# final-board.net
KiCad netlist of a schematic drawn in EAGLE
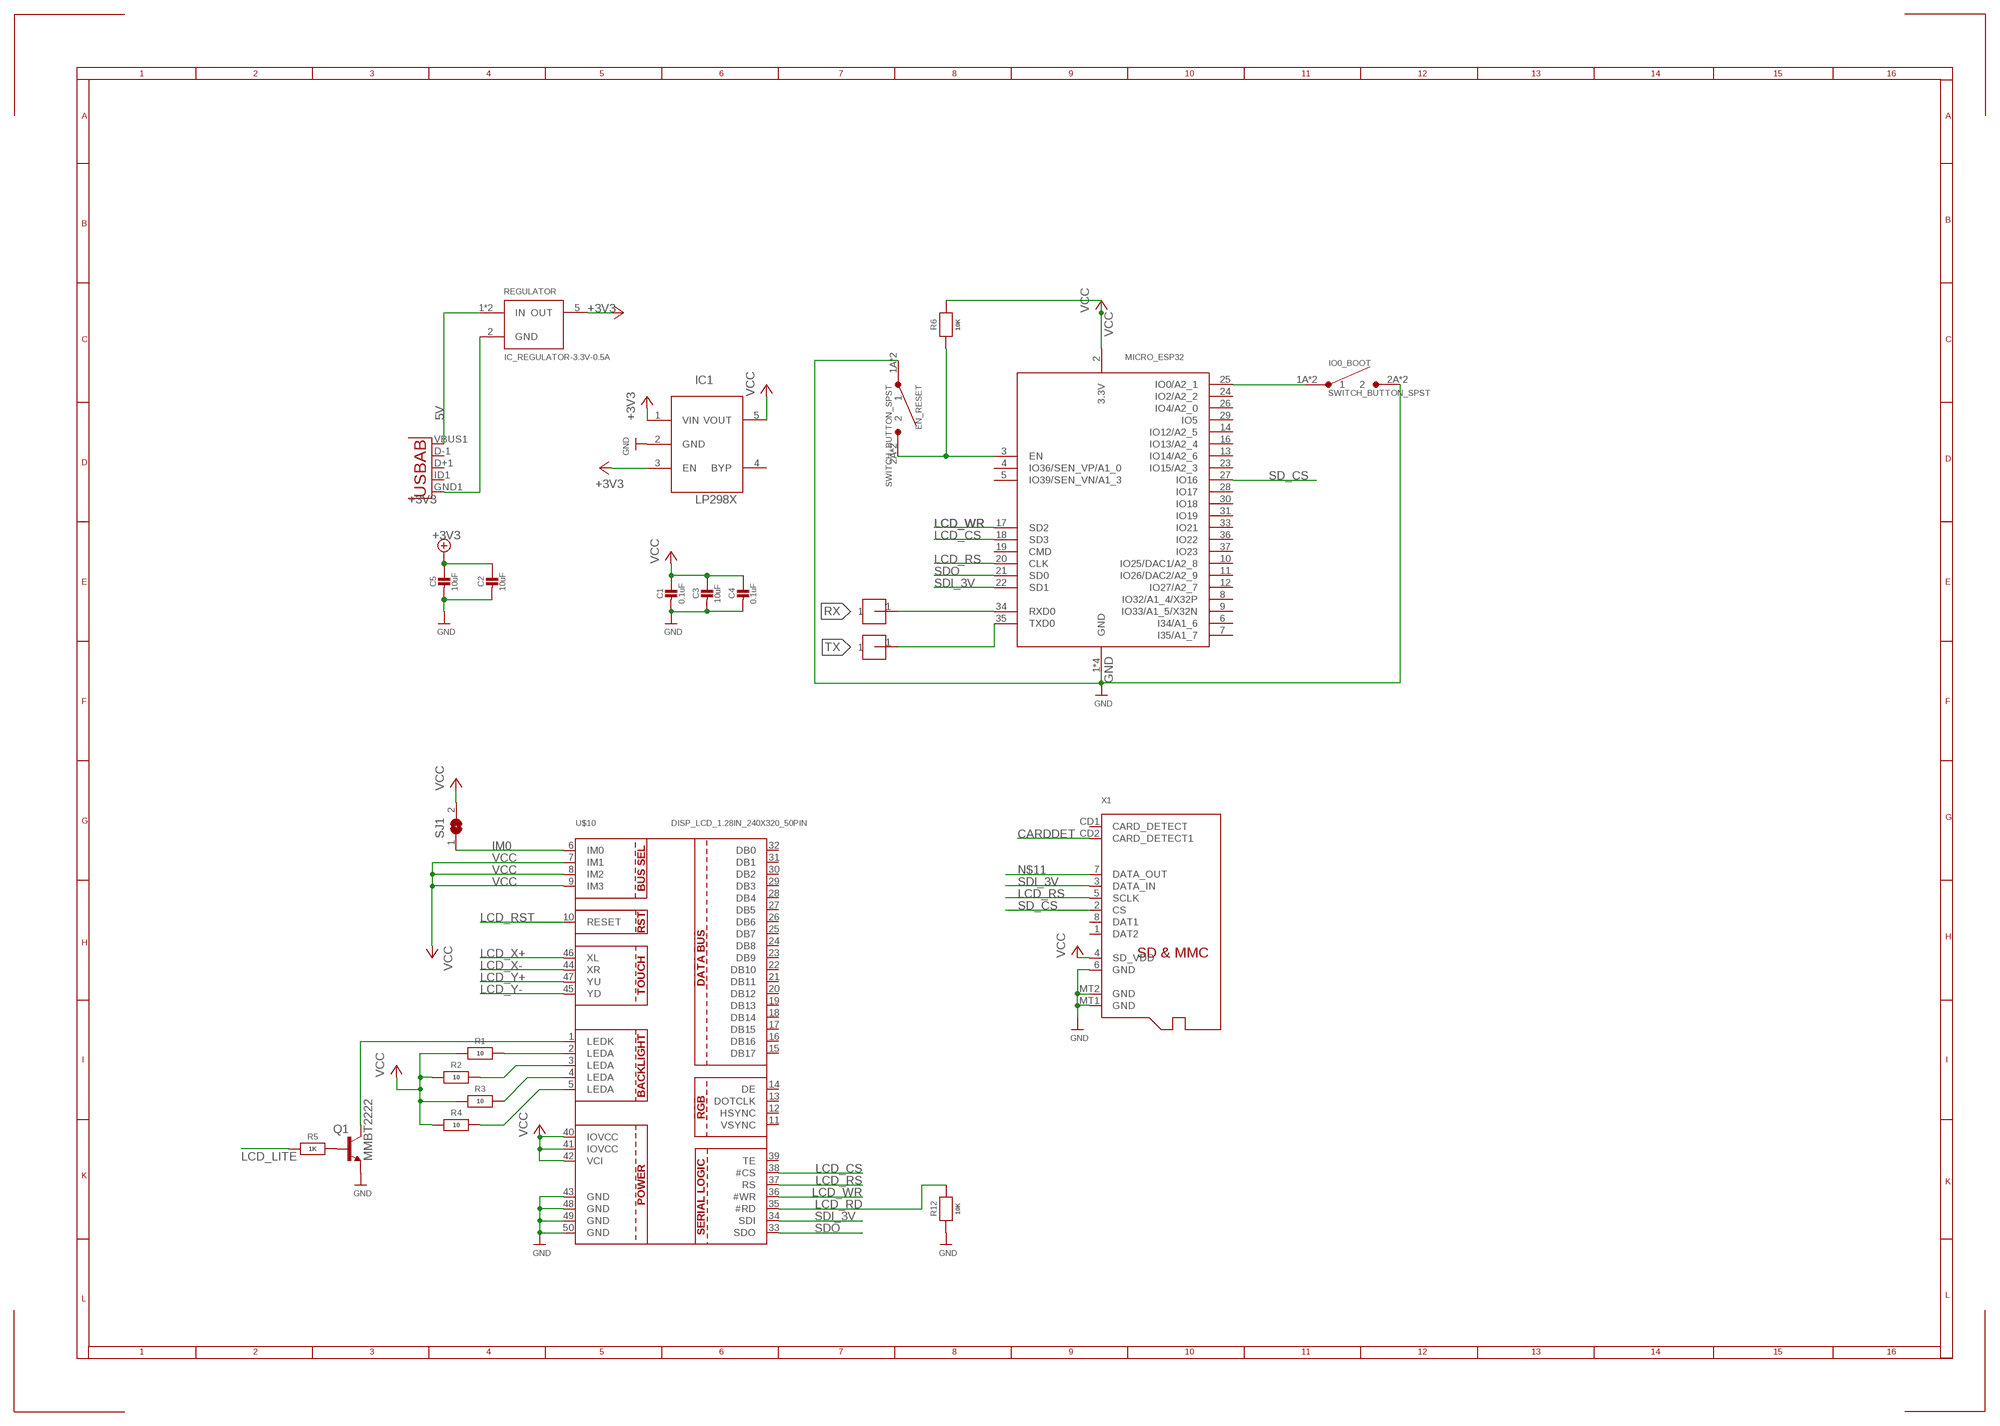
[diagram p0: schematic, sheet 1]

(export (version "E")
  (design (tool "Eeschema 10.0.6"))
  (components
    (comp (ref "C1")
      (value "0.1uF")
      (footprint "eagle-import:0805-NO")
      (libsource (lib "eagle-import") (part "CAP_CERAMIC0805-NOOUTLINE"))
    )
    (comp (ref "C2")
      (value "10uF")
      (footprint "eagle-import:0805-NO")
      (libsource (lib "eagle-import") (part "CAP_CERAMIC0805-NOOUTLINE"))
    )
    (comp (ref "C3")
      (value "10uF")
      (footprint "eagle-import:0805-NO")
      (libsource (lib "eagle-import") (part "CAP_CERAMIC0805-NOOUTLINE"))
    )
    (comp (ref "C4")
      (value "0.1uF")
      (footprint "eagle-import:0805-NO")
      (libsource (lib "eagle-import") (part "CAP_CERAMIC0805-NOOUTLINE"))
    )
    (comp (ref "C5")
      (value "10uF")
      (footprint "eagle-import:0805-NO")
      (libsource (lib "eagle-import") (part "CAP_CERAMIC0805-NOOUTLINE"))
    )
    (comp (ref "EN_RESET")
      (value "SWITCH_BUTTON_SPST")
      (footprint "eagle-import:7914G-1-000E")
      (libsource (lib "eagle-import") (part "SWITCH_BUTTON_SPST"))
    )
    (comp (ref "ESP_32")
      (value "MICRO_ESP32")
      (footprint "eagle-import:WROOM32")
      (libsource (lib "eagle-import") (part "MICRO_ESP32"))
    )
    (comp (ref "IC1")
      (value "MIC5225-3.3")
      (footprint "eagle-import:SOT23-5L")
      (libsource (lib "eagle-import") (part "LP298XS"))
    )
    (comp (ref "IO0_BOOT")
      (value "SWITCH_BUTTON_SPST")
      (footprint "eagle-import:7914G-1-000E")
      (libsource (lib "eagle-import") (part "SWITCH_BUTTON_SPST"))
    )
    (comp (ref "Q1")
      (value "MMBT2222")
      (footprint "eagle-import:SOT23-BEC")
      (libsource (lib "eagle-import") (part "-NPN-SOT23-BECMMBT2222ALT1"))
    )
    (comp (ref "R1")
      (value "10")
      (footprint "eagle-import:0805-NO")
      (libsource (lib "eagle-import") (part "RESISTOR0805_NOOUTLINE"))
    )
    (comp (ref "R2")
      (value "10")
      (footprint "eagle-import:0805-NO")
      (libsource (lib "eagle-import") (part "RESISTOR0805_NOOUTLINE"))
    )
    (comp (ref "R3")
      (value "10")
      (footprint "eagle-import:0805-NO")
      (libsource (lib "eagle-import") (part "RESISTOR0805_NOOUTLINE"))
    )
    (comp (ref "R4")
      (value "10")
      (footprint "eagle-import:0805-NO")
      (libsource (lib "eagle-import") (part "RESISTOR0805_NOOUTLINE"))
    )
    (comp (ref "R5")
      (value "1K")
      (footprint "eagle-import:0805-NO")
      (libsource (lib "eagle-import") (part "RESISTOR0805_NOOUTLINE"))
    )
    (comp (ref "R6")
      (value "10K")
      (footprint "eagle-import:0805-NO")
      (libsource (lib "eagle-import") (part "RESISTOR0805_NOOUTLINE"))
    )
    (comp (ref "R12")
      (value "10K")
      (footprint "eagle-import:0805-NO")
      (libsource (lib "eagle-import") (part "RESISTOR0805_NOOUTLINE"))
    )
    (comp (ref "REGULATOR")
      (value "IC_REGULATOR-3.3V-0.5A")
      (footprint "eagle-import:SOT23-5")
      (libsource (lib "eagle-import") (part "IC_REGULATOR-3.3V-0.5A"))
    )
    (comp (ref "SJ1")
      (value "SOLDERJUMPER")
      (footprint "eagle-import:SOLDERJUMPER_ARROW_NOPASTE")
      (libsource (lib "eagle-import") (part "SOLDERJUMPER"))
    )
    (comp (ref "U$2")
      (value "HEADER-1-TESTPOINT")
      (footprint "eagle-import:TESTPOINT-1")
      (libsource (lib "eagle-import") (part "HEADER-1-TESTPOINT"))
    )
    (comp (ref "U$7")
      (value "HEADER-1-TESTPOINT")
      (footprint "eagle-import:TESTPOINT-1")
      (libsource (lib "eagle-import") (part "HEADER-1-TESTPOINT"))
    )
    (comp (ref "U$10")
      (value "DISP_LCD_1.28IN_240X320_50PIN")
      (footprint "eagle-import:TFT_2.83IN_240X320_50PIN")
      (libsource (lib "eagle-import") (part "DISP_LCD_1.28IN_240X320_50PIN"))
    )
    (comp (ref "USB")
      (value "USB\"\"")
      (footprint "eagle-import:USB-MICRO-SMD")
      (libsource (lib "eagle-import") (part "USB{dblquote}{dblquote}"))
    )
    (comp (ref "X1")
      (value "MICROSD")
      (footprint "eagle-import:MICROSD")
      (libsource (lib "eagle-import") (part "MICROSD"))
    )
  )
  (nets
    (net (code "1") (name "+3V3") (class "Default")
      (node (ref "C2") (pin "1") (pinfunction "1_1") (pintype "passive"))
      (node (ref "C5") (pin "1") (pinfunction "1_1") (pintype "passive"))
      (node (ref "IC1") (pin "1") (pinfunction "VIN_1") (pintype "bidirectional"))
      (node (ref "IC1") (pin "3") (pinfunction "EN_3") (pintype "bidirectional"))
      (node (ref "REGULATOR") (pin "5") (pinfunction "OUT_5") (pintype "bidirectional"))
    )
    (net (code "2") (name "/5V") (class "Default")
      (node (ref "REGULATOR") (pin "1") (pinfunction "IN_1") (pintype "bidirectional"))
      (node (ref "REGULATOR") (pin "3") (pinfunction "IN_3") (pintype "bidirectional"))
      (node (ref "USB") (pin "VBUS1") (pinfunction "VBUS_VBUS1") (pintype "bidirectional"))
    )
    (net (code "3") (name "/CARDDET") (class "Default")
      (node (ref "X1") (pin "CD2") (pinfunction "CARD_DETECT1_CD2") (pintype "passive"))
    )
    (net (code "4") (name "/IM0") (class "Default")
      (node (ref "SJ1") (pin "1") (pinfunction "1_1") (pintype "passive"))
      (node (ref "U$10") (pin "6") (pinfunction "IM0_6") (pintype "bidirectional"))
    )
    (net (code "5") (name "/LCD_CS") (class "Default")
      (node (ref "ESP_32") (pin "18") (pinfunction "SD3_18") (pintype "bidirectional"))
      (node (ref "U$10") (pin "38") (pinfunction "#CS_38") (pintype "bidirectional"))
    )
    (net (code "6") (name "/LCD_LITE") (class "Default")
      (node (ref "R5") (pin "1") (pinfunction "1_1") (pintype "passive"))
    )
    (net (code "7") (name "/LCD_RD") (class "Default")
      (node (ref "R12") (pin "2") (pinfunction "2_2") (pintype "passive"))
      (node (ref "U$10") (pin "35") (pinfunction "#RD_35") (pintype "bidirectional"))
    )
    (net (code "8") (name "/LCD_RS") (class "Default")
      (node (ref "ESP_32") (pin "20") (pinfunction "CLK_20") (pintype "bidirectional"))
      (node (ref "U$10") (pin "37") (pinfunction "RS_37") (pintype "bidirectional"))
      (node (ref "X1") (pin "5") (pinfunction "SCLK_5") (pintype "input"))
    )
    (net (code "9") (name "/LCD_RST") (class "Default")
      (node (ref "U$10") (pin "10") (pinfunction "RESET_10") (pintype "bidirectional"))
    )
    (net (code "10") (name "/LCD_WR") (class "Default")
      (node (ref "ESP_32") (pin "17") (pinfunction "SD2_17") (pintype "bidirectional"))
      (node (ref "U$10") (pin "36") (pinfunction "#WR_36") (pintype "bidirectional"))
    )
    (net (code "11") (name "/LCD_X+") (class "Default")
      (node (ref "U$10") (pin "46") (pinfunction "XL_46") (pintype "bidirectional"))
    )
    (net (code "12") (name "/LCD_X-") (class "Default")
      (node (ref "U$10") (pin "44") (pinfunction "XR_44") (pintype "bidirectional"))
    )
    (net (code "13") (name "/LCD_Y+") (class "Default")
      (node (ref "U$10") (pin "47") (pinfunction "YU_47") (pintype "bidirectional"))
    )
    (net (code "14") (name "/LCD_Y-") (class "Default")
      (node (ref "U$10") (pin "45") (pinfunction "YD_45") (pintype "bidirectional"))
    )
    (net (code "15") (name "/N$11") (class "Default")
      (node (ref "X1") (pin "7") (pinfunction "DATA_OUT_7") (pintype "output"))
    )
    (net (code "16") (name "/SDI_3V") (class "Default")
      (node (ref "ESP_32") (pin "22") (pinfunction "SD1_22") (pintype "bidirectional"))
      (node (ref "U$10") (pin "34") (pinfunction "SDI_34") (pintype "bidirectional"))
      (node (ref "X1") (pin "3") (pinfunction "DATA_IN_3") (pintype "input"))
    )
    (net (code "17") (name "/SDO") (class "Default")
      (node (ref "ESP_32") (pin "21") (pinfunction "SD0_21") (pintype "bidirectional"))
      (node (ref "U$10") (pin "33") (pinfunction "SDO_33") (pintype "bidirectional"))
    )
    (net (code "18") (name "/SD_CS") (class "Default")
      (node (ref "ESP_32") (pin "27") (pinfunction "IO16_27") (pintype "bidirectional"))
      (node (ref "X1") (pin "2") (pinfunction "CS_2") (pintype "input"))
    )
    (net (code "19") (name "GND") (class "Default")
      (node (ref "C1") (pin "2") (pinfunction "2_2") (pintype "passive"))
      (node (ref "C2") (pin "2") (pinfunction "2_2") (pintype "passive"))
      (node (ref "C3") (pin "2") (pinfunction "2_2") (pintype "passive"))
      (node (ref "C4") (pin "2") (pinfunction "2_2") (pintype "passive"))
      (node (ref "C5") (pin "2") (pinfunction "2_2") (pintype "passive"))
      (node (ref "EN_RESET") (pin "1A") (pinfunction "1_1A") (pintype "bidirectional"))
      (node (ref "EN_RESET") (pin "1B") (pinfunction "1_1B") (pintype "bidirectional"))
      (node (ref "ESP_32") (pin "1") (pinfunction "GND_1") (pintype "passive"))
      (node (ref "ESP_32") (pin "15") (pinfunction "GND_15") (pintype "passive"))
      (node (ref "ESP_32") (pin "38") (pinfunction "GND_38") (pintype "passive"))
      (node (ref "ESP_32") (pin "P$1") (pinfunction "GND_P$1") (pintype "passive"))
      (node (ref "IC1") (pin "2") (pinfunction "GND_2") (pintype "bidirectional"))
      (node (ref "IO0_BOOT") (pin "2A") (pinfunction "2_2A") (pintype "bidirectional"))
      (node (ref "IO0_BOOT") (pin "2B") (pinfunction "2_2B") (pintype "bidirectional"))
      (node (ref "Q1") (pin "E") (pinfunction "E_E") (pintype "passive"))
      (node (ref "R12") (pin "1") (pinfunction "1_1") (pintype "passive"))
      (node (ref "REGULATOR") (pin "2") (pinfunction "GND_2") (pintype "bidirectional"))
      (node (ref "U$10") (pin "43") (pinfunction "GND_43") (pintype "bidirectional"))
      (node (ref "U$10") (pin "48") (pinfunction "GND_48") (pintype "bidirectional"))
      (node (ref "U$10") (pin "49") (pinfunction "GND_49") (pintype "bidirectional"))
      (node (ref "U$10") (pin "50") (pinfunction "GND_50") (pintype "bidirectional"))
      (node (ref "USB") (pin "GND1") (pinfunction "GND_GND1") (pintype "bidirectional"))
      (node (ref "X1") (pin "6") (pinfunction "GND_6") (pintype "power_in"))
      (node (ref "X1") (pin "MT1") (pinfunction "GND_MT1") (pintype "power_in"))
      (node (ref "X1") (pin "MT2") (pinfunction "GND_MT2") (pintype "power_in"))
    )
    (net (code "20") (name "Net-(ESP_32-EN)") (class "Default")
      (node (ref "EN_RESET") (pin "2A") (pinfunction "2_2A") (pintype "bidirectional"))
      (node (ref "EN_RESET") (pin "2B") (pinfunction "2_2B") (pintype "bidirectional"))
      (node (ref "ESP_32") (pin "3") (pinfunction "EN_3") (pintype "input"))
      (node (ref "R6") (pin "1") (pinfunction "1_1") (pintype "passive"))
    )
    (net (code "21") (name "Net-(ESP_32-IO0{slash}A2_1)") (class "Default")
      (node (ref "ESP_32") (pin "25") (pinfunction "IO0/A2_1_25") (pintype "bidirectional"))
      (node (ref "IO0_BOOT") (pin "1A") (pinfunction "1_1A") (pintype "bidirectional"))
      (node (ref "IO0_BOOT") (pin "1B") (pinfunction "1_1B") (pintype "bidirectional"))
    )
    (net (code "22") (name "Net-(Q1-PadB)") (class "Default")
      (node (ref "Q1") (pin "B") (pinfunction "B_B") (pintype "passive"))
      (node (ref "R5") (pin "2") (pinfunction "2_2") (pintype "passive"))
    )
    (net (code "23") (name "Net-(R1-Pad2)") (class "Default")
      (node (ref "R1") (pin "2") (pinfunction "2_2") (pintype "passive"))
      (node (ref "U$10") (pin "2") (pinfunction "LEDA_2") (pintype "bidirectional"))
    )
    (net (code "24") (name "Net-(R2-Pad2)") (class "Default")
      (node (ref "R2") (pin "2") (pinfunction "2_2") (pintype "passive"))
      (node (ref "U$10") (pin "3") (pinfunction "LEDA_3") (pintype "bidirectional"))
    )
    (net (code "25") (name "Net-(R3-Pad2)") (class "Default")
      (node (ref "R3") (pin "2") (pinfunction "2_2") (pintype "passive"))
      (node (ref "U$10") (pin "4") (pinfunction "LEDA_4") (pintype "bidirectional"))
    )
    (net (code "26") (name "Net-(R4-Pad2)") (class "Default")
      (node (ref "R4") (pin "2") (pinfunction "2_2") (pintype "passive"))
      (node (ref "U$10") (pin "5") (pinfunction "LEDA_5") (pintype "bidirectional"))
    )
    (net (code "27") (name "Net-(U$10-LEDK)") (class "Default")
      (node (ref "Q1") (pin "C") (pinfunction "C_C") (pintype "passive"))
      (node (ref "U$10") (pin "1") (pinfunction "LEDK_1") (pintype "bidirectional"))
    )
    (net (code "28") (name "RX") (class "Default")
      (node (ref "ESP_32") (pin "34") (pinfunction "RXD0_34") (pintype "input"))
      (node (ref "U$2") (pin "1") (pinfunction "1_1") (pintype "bidirectional"))
    )
    (net (code "29") (name "TX") (class "Default")
      (node (ref "ESP_32") (pin "35") (pinfunction "TXD0_35") (pintype "output"))
      (node (ref "U$7") (pin "1") (pinfunction "1_1") (pintype "bidirectional"))
    )
    (net (code "30") (name "VCC") (class "Default")
      (node (ref "C1") (pin "1") (pinfunction "1_1") (pintype "passive"))
      (node (ref "C3") (pin "1") (pinfunction "1_1") (pintype "passive"))
      (node (ref "C4") (pin "1") (pinfunction "1_1") (pintype "passive"))
      (node (ref "ESP_32") (pin "2") (pinfunction "3.3V_2") (pintype "passive"))
      (node (ref "IC1") (pin "5") (pinfunction "VOUT_5") (pintype "bidirectional"))
      (node (ref "R1") (pin "1") (pinfunction "1_1") (pintype "passive"))
      (node (ref "R2") (pin "1") (pinfunction "1_1") (pintype "passive"))
      (node (ref "R3") (pin "1") (pinfunction "1_1") (pintype "passive"))
      (node (ref "R4") (pin "1") (pinfunction "1_1") (pintype "passive"))
      (node (ref "R6") (pin "2") (pinfunction "2_2") (pintype "passive"))
      (node (ref "SJ1") (pin "2") (pinfunction "2_2") (pintype "passive"))
      (node (ref "U$10") (pin "40") (pinfunction "IOVCC_40") (pintype "bidirectional"))
      (node (ref "U$10") (pin "41") (pinfunction "IOVCC_41") (pintype "bidirectional"))
      (node (ref "U$10") (pin "42") (pinfunction "VCI_42") (pintype "bidirectional"))
      (node (ref "U$10") (pin "7") (pinfunction "IM1_7") (pintype "bidirectional"))
      (node (ref "U$10") (pin "8") (pinfunction "IM2_8") (pintype "bidirectional"))
      (node (ref "U$10") (pin "9") (pinfunction "IM3_9") (pintype "bidirectional"))
      (node (ref "X1") (pin "4") (pinfunction "SD_VDD_4") (pintype "power_in"))
    )
    (net (code "31") (name "unconnected-(ESP_32-CMD-Pad19)") (class "Default")
      (node (ref "ESP_32") (pin "19") (pinfunction "CMD_19") (pintype "bidirectional"))
    )
    (net (code "32") (name "unconnected-(ESP_32-I34{slash}A1_6-Pad6)") (class "Default")
      (node (ref "ESP_32") (pin "6") (pinfunction "I34/A1_6_6") (pintype "bidirectional"))
    )
    (net (code "33") (name "unconnected-(ESP_32-I35{slash}A1_7-Pad7)") (class "Default")
      (node (ref "ESP_32") (pin "7") (pinfunction "I35/A1_7_7") (pintype "bidirectional"))
    )
    (net (code "34") (name "unconnected-(ESP_32-IO2{slash}A2_2-Pad24)") (class "Default")
      (node (ref "ESP_32") (pin "24") (pinfunction "IO2/A2_2_24") (pintype "bidirectional"))
    )
    (net (code "35") (name "unconnected-(ESP_32-IO4{slash}A2_0-Pad26)") (class "Default")
      (node (ref "ESP_32") (pin "26") (pinfunction "IO4/A2_0_26") (pintype "bidirectional"))
    )
    (net (code "36") (name "unconnected-(ESP_32-IO5-Pad29)") (class "Default")
      (node (ref "ESP_32") (pin "29") (pinfunction "IO5_29") (pintype "bidirectional"))
    )
    (net (code "37") (name "unconnected-(ESP_32-IO12{slash}A2_5-Pad14)") (class "Default")
      (node (ref "ESP_32") (pin "14") (pinfunction "IO12/A2_5_14") (pintype "bidirectional"))
    )
    (net (code "38") (name "unconnected-(ESP_32-IO13{slash}A2_4-Pad16)") (class "Default")
      (node (ref "ESP_32") (pin "16") (pinfunction "IO13/A2_4_16") (pintype "bidirectional"))
    )
    (net (code "39") (name "unconnected-(ESP_32-IO14{slash}A2_6-Pad13)") (class "Default")
      (node (ref "ESP_32") (pin "13") (pinfunction "IO14/A2_6_13") (pintype "bidirectional"))
    )
    (net (code "40") (name "unconnected-(ESP_32-IO15{slash}A2_3-Pad23)") (class "Default")
      (node (ref "ESP_32") (pin "23") (pinfunction "IO15/A2_3_23") (pintype "bidirectional"))
    )
    (net (code "41") (name "unconnected-(ESP_32-IO17-Pad28)") (class "Default")
      (node (ref "ESP_32") (pin "28") (pinfunction "IO17_28") (pintype "bidirectional"))
    )
    (net (code "42") (name "unconnected-(ESP_32-IO18-Pad30)") (class "Default")
      (node (ref "ESP_32") (pin "30") (pinfunction "IO18_30") (pintype "bidirectional"))
    )
    (net (code "43") (name "unconnected-(ESP_32-IO19-Pad31)") (class "Default")
      (node (ref "ESP_32") (pin "31") (pinfunction "IO19_31") (pintype "bidirectional"))
    )
    (net (code "44") (name "unconnected-(ESP_32-IO21-Pad33)") (class "Default")
      (node (ref "ESP_32") (pin "33") (pinfunction "IO21_33") (pintype "bidirectional"))
    )
    (net (code "45") (name "unconnected-(ESP_32-IO22-Pad36)") (class "Default")
      (node (ref "ESP_32") (pin "36") (pinfunction "IO22_36") (pintype "bidirectional"))
    )
    (net (code "46") (name "unconnected-(ESP_32-IO23-Pad37)") (class "Default")
      (node (ref "ESP_32") (pin "37") (pinfunction "IO23_37") (pintype "bidirectional"))
    )
    (net (code "47") (name "unconnected-(ESP_32-IO25{slash}DAC1{slash}A2_8-Pad10)") (class "Default")
      (node (ref "ESP_32") (pin "10") (pinfunction "IO25/DAC1/A2_8_10") (pintype "bidirectional"))
    )
    (net (code "48") (name "unconnected-(ESP_32-IO26{slash}DAC2{slash}A2_9-Pad11)") (class "Default")
      (node (ref "ESP_32") (pin "11") (pinfunction "IO26/DAC2/A2_9_11") (pintype "bidirectional"))
    )
    (net (code "49") (name "unconnected-(ESP_32-IO27{slash}A2_7-Pad12)") (class "Default")
      (node (ref "ESP_32") (pin "12") (pinfunction "IO27/A2_7_12") (pintype "bidirectional"))
    )
    (net (code "50") (name "unconnected-(ESP_32-IO32{slash}A1_4{slash}X32P-Pad8)") (class "Default")
      (node (ref "ESP_32") (pin "8") (pinfunction "IO32/A1_4/X32P_8") (pintype "bidirectional"))
    )
    (net (code "51") (name "unconnected-(ESP_32-IO33{slash}A1_5{slash}X32N-Pad9)") (class "Default")
      (node (ref "ESP_32") (pin "9") (pinfunction "IO33/A1_5/X32N_9") (pintype "bidirectional"))
    )
    (net (code "52") (name "unconnected-(ESP_32-IO36{slash}SEN_VP{slash}A1_0-Pad4)") (class "Default")
      (node (ref "ESP_32") (pin "4") (pinfunction "IO36/SEN_VP/A1_0_4") (pintype "passive"))
    )
    (net (code "53") (name "unconnected-(ESP_32-IO39{slash}SEN_VN{slash}A1_3-Pad5)") (class "Default")
      (node (ref "ESP_32") (pin "5") (pinfunction "IO39/SEN_VN/A1_3_5") (pintype "passive"))
    )
    (net (code "54") (name "unconnected-(IC1-BYP-Pad4)") (class "Default")
      (node (ref "IC1") (pin "4") (pinfunction "BYP_4") (pintype "bidirectional"))
    )
    (net (code "55") (name "unconnected-(U$10-DB0-Pad32)") (class "Default")
      (node (ref "U$10") (pin "32") (pinfunction "DB0_32") (pintype "bidirectional"))
    )
    (net (code "56") (name "unconnected-(U$10-DB1-Pad31)") (class "Default")
      (node (ref "U$10") (pin "31") (pinfunction "DB1_31") (pintype "bidirectional"))
    )
    (net (code "57") (name "unconnected-(U$10-DB2-Pad30)") (class "Default")
      (node (ref "U$10") (pin "30") (pinfunction "DB2_30") (pintype "bidirectional"))
    )
    (net (code "58") (name "unconnected-(U$10-DB3-Pad29)") (class "Default")
      (node (ref "U$10") (pin "29") (pinfunction "DB3_29") (pintype "bidirectional"))
    )
    (net (code "59") (name "unconnected-(U$10-DB4-Pad28)") (class "Default")
      (node (ref "U$10") (pin "28") (pinfunction "DB4_28") (pintype "bidirectional"))
    )
    (net (code "60") (name "unconnected-(U$10-DB5-Pad27)") (class "Default")
      (node (ref "U$10") (pin "27") (pinfunction "DB5_27") (pintype "bidirectional"))
    )
    (net (code "61") (name "unconnected-(U$10-DB6-Pad26)") (class "Default")
      (node (ref "U$10") (pin "26") (pinfunction "DB6_26") (pintype "bidirectional"))
    )
    (net (code "62") (name "unconnected-(U$10-DB7-Pad25)") (class "Default")
      (node (ref "U$10") (pin "25") (pinfunction "DB7_25") (pintype "bidirectional"))
    )
    (net (code "63") (name "unconnected-(U$10-DB8-Pad24)") (class "Default")
      (node (ref "U$10") (pin "24") (pinfunction "DB8_24") (pintype "bidirectional"))
    )
    (net (code "64") (name "unconnected-(U$10-DB9-Pad23)") (class "Default")
      (node (ref "U$10") (pin "23") (pinfunction "DB9_23") (pintype "bidirectional"))
    )
    (net (code "65") (name "unconnected-(U$10-DB10-Pad22)") (class "Default")
      (node (ref "U$10") (pin "22") (pinfunction "DB10_22") (pintype "bidirectional"))
    )
    (net (code "66") (name "unconnected-(U$10-DB11-Pad21)") (class "Default")
      (node (ref "U$10") (pin "21") (pinfunction "DB11_21") (pintype "bidirectional"))
    )
    (net (code "67") (name "unconnected-(U$10-DB12-Pad20)") (class "Default")
      (node (ref "U$10") (pin "20") (pinfunction "DB12_20") (pintype "bidirectional"))
    )
    (net (code "68") (name "unconnected-(U$10-DB13-Pad19)") (class "Default")
      (node (ref "U$10") (pin "19") (pinfunction "DB13_19") (pintype "bidirectional"))
    )
    (net (code "69") (name "unconnected-(U$10-DB14-Pad18)") (class "Default")
      (node (ref "U$10") (pin "18") (pinfunction "DB14_18") (pintype "bidirectional"))
    )
    (net (code "70") (name "unconnected-(U$10-DB15-Pad17)") (class "Default")
      (node (ref "U$10") (pin "17") (pinfunction "DB15_17") (pintype "bidirectional"))
    )
    (net (code "71") (name "unconnected-(U$10-DB16-Pad16)") (class "Default")
      (node (ref "U$10") (pin "16") (pinfunction "DB16_16") (pintype "bidirectional"))
    )
    (net (code "72") (name "unconnected-(U$10-DB17-Pad15)") (class "Default")
      (node (ref "U$10") (pin "15") (pinfunction "DB17_15") (pintype "bidirectional"))
    )
    (net (code "73") (name "unconnected-(U$10-DE-Pad14)") (class "Default")
      (node (ref "U$10") (pin "14") (pinfunction "DE_14") (pintype "bidirectional"))
    )
    (net (code "74") (name "unconnected-(U$10-DOTCLK-Pad13)") (class "Default")
      (node (ref "U$10") (pin "13") (pinfunction "DOTCLK_13") (pintype "bidirectional"))
    )
    (net (code "75") (name "unconnected-(U$10-HSYNC-Pad12)") (class "Default")
      (node (ref "U$10") (pin "12") (pinfunction "HSYNC_12") (pintype "bidirectional"))
    )
    (net (code "76") (name "unconnected-(U$10-TE-Pad39)") (class "Default")
      (node (ref "U$10") (pin "39") (pinfunction "TE_39") (pintype "bidirectional"))
    )
    (net (code "77") (name "unconnected-(U$10-VSYNC-Pad11)") (class "Default")
      (node (ref "U$10") (pin "11") (pinfunction "VSYNC_11") (pintype "bidirectional"))
    )
    (net (code "78") (name "unconnected-(USB-D+-PadD+1)") (class "Default")
      (node (ref "USB") (pin "D+1") (pinfunction "D+_D+1") (pintype "bidirectional"))
    )
    (net (code "79") (name "unconnected-(USB-D--PadD-1)") (class "Default")
      (node (ref "USB") (pin "D-1") (pinfunction "D-_D-1") (pintype "bidirectional"))
    )
    (net (code "80") (name "unconnected-(USB-USBID-PadID1)") (class "Default")
      (node (ref "USB") (pin "ID1") (pinfunction "USBID_ID1") (pintype "bidirectional"))
    )
    (net (code "81") (name "unconnected-(X1-CARD_DETECT-PadCD1)") (class "Default")
      (node (ref "X1") (pin "CD1") (pinfunction "CARD_DETECT_CD1") (pintype "passive"))
    )
    (net (code "82") (name "unconnected-(X1-DAT1-Pad8)") (class "Default")
      (node (ref "X1") (pin "8") (pinfunction "DAT1_8") (pintype "bidirectional"))
    )
    (net (code "83") (name "unconnected-(X1-DAT2-Pad1)") (class "Default")
      (node (ref "X1") (pin "1") (pinfunction "DAT2_1") (pintype "bidirectional"))
    )
  )
)
